# LT6813.net
KiCad netlist of a schematic drawn in Altium Designer
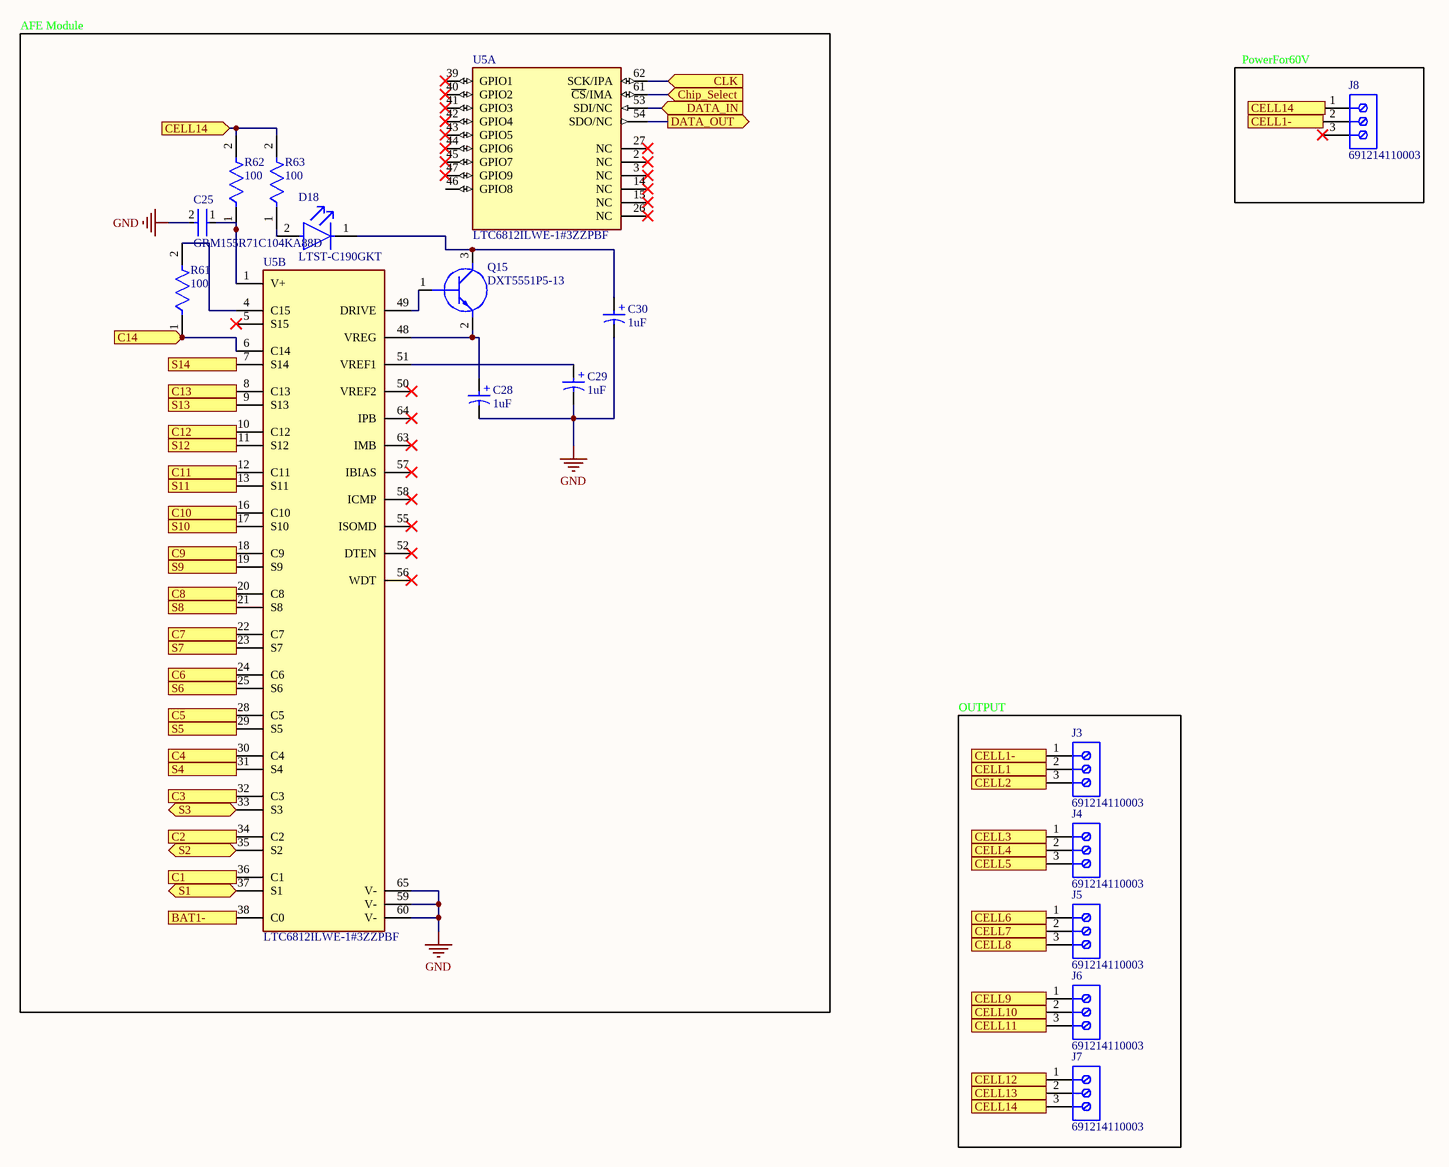
[diagram p0: LT6813.SchDoc]

(export (version "E")
  (design (tool "Eeschema 10.0.6"))
  (components
    (comp (ref "C25")
      (value "GRM155R71C104KA88D")
      (footprint "FP-GRM15-MFG")
      (description "CAP CER 0.1UF 16V X7R 0402")
      (fields
        (field (name "TOLERANCE") "10%")
        (field (name "OCTOPART") "https://octopart.com/grm155r71c104ka88d-murata-196880")
      )
      (libsource (lib "Altium Content Vault") (part "236180d848d6139a670b325ea6854c9"))
    )
    (comp (ref "C28")
      (value "1uF")
      (footprint "WCAP-ASLI_D4H5.5")
      (description "865080840001 Cap, 1Uf, 20%, 100V, Alu Elec Smd Rohs Compliant: Yes")
      (libsource (lib "Altium Content Vault") (part "Capacitor_Polarized"))
    )
    (comp (ref "C29")
      (value "1uF")
      (footprint "WCAP-ASLI_D4H5.5")
      (description "865080840001 Cap, 1Uf, 20%, 100V, Alu Elec Smd Rohs Compliant: Yes")
      (libsource (lib "Altium Content Vault") (part "Capacitor_Polarized"))
    )
    (comp (ref "C30")
      (value "1uF")
      (footprint "WCAP-ASLI_D4H5.5")
      (description "865080840001 Cap, 1Uf, 20%, 100V, Alu Elec Smd Rohs Compliant: Yes")
      (libsource (lib "Altium Content Vault") (part "Capacitor_Polarized"))
    )
    (comp (ref "D18")
      (value "LTST-C190GKT")
      (footprint "FP-LTST-C190GKT-MFG")
      (description "LED GREEN CLEAR CHIP SMD")
      (fields (field (name "VOLTAGE") "2V"))
      (libsource (lib "Altium Content Vault") (part "8706943c75ba83719d021d2fdc84c58"))
    )
    (comp (ref "J3")
      (value "691214110003")
      (footprint "691214110003")
      (fields (field (name "VOLTAGE") "300V"))
      (libsource (lib "Altium Content Vault") (part "TBL - 1R - 03P - Screw"))
    )
    (comp (ref "J4")
      (value "691214110003")
      (footprint "691214110003")
      (fields (field (name "VOLTAGE") "300V"))
      (libsource (lib "Altium Content Vault") (part "TBL - 1R - 03P - Screw"))
    )
    (comp (ref "J5")
      (value "691214110003")
      (footprint "691214110003")
      (fields (field (name "VOLTAGE") "300V"))
      (libsource (lib "Altium Content Vault") (part "TBL - 1R - 03P - Screw"))
    )
    (comp (ref "J6")
      (value "691214110003")
      (footprint "691214110003")
      (fields (field (name "VOLTAGE") "300V"))
      (libsource (lib "Altium Content Vault") (part "TBL - 1R - 03P - Screw"))
    )
    (comp (ref "J7")
      (value "691214110003")
      (footprint "691214110003")
      (fields (field (name "VOLTAGE") "300V"))
      (libsource (lib "Altium Content Vault") (part "TBL - 1R - 03P - Screw"))
    )
    (comp (ref "J8")
      (value "691214110003")
      (footprint "691214110003")
      (fields (field (name "VOLTAGE") "300V"))
      (libsource (lib "Altium Content Vault") (part "TBL - 1R - 03P - Screw"))
    )
    (comp (ref "Q15")
      (value "DXT5551P5-13")
      (footprint "SamacSys:DXT5551P513")
      (description "Transistor BJT NPN")
      (fields (field (name "MOUSER PART NUMBER") "522-DXT5551P5-13"))
      (libsource (lib "*") (part "DXT5551P5-13"))
    )
    (comp (ref "R61")
      (value "100")
      (footprint "FP-RR0816-MFG")
      (description "100Ω ±0.5% 0.0625W 1/16W Chip Resistor 0603 (1608 Metric) Thin Film")
      (fields (field (name "TOLERANCE") "0.5%"))
      (libsource (lib "Altium Content Vault") (part "1029c3af85768c4190bb7ad29bc67b5"))
    )
    (comp (ref "R62")
      (value "100")
      (footprint "FP-RR0816-MFG")
      (description "100Ω ±0.5% 0.0625W 1/16W Chip Resistor 0603 (1608 Metric) Thin Film")
      (fields (field (name "TOLERANCE") "0.5%"))
      (libsource (lib "Altium Content Vault") (part "1029c3af85768c4190bb7ad29bc67b5"))
    )
    (comp (ref "R63")
      (value "100")
      (footprint "FP-RR0816-MFG")
      (description "100Ω ±0.5% 0.0625W 1/16W Chip Resistor 0603 (1608 Metric) Thin Film")
      (fields (field (name "TOLERANCE") "0.5%"))
      (libsource (lib "Altium Content Vault") (part "1029c3af85768c4190bb7ad29bc67b5"))
    )
    (comp (ref "U5")
      (value "LTC6812ILWE-1#3ZZPBF")
      (footprint "FP-LWE-64-05-08-1982-MFG")
      (description "MULTICELL BAT MON S")
      (fields
        (field (name "MANUFACTURER") "Analog Devices")
        (field (name "OCTOPART") "https://octopart.com/ltc6812ilwe-1%233zzpbf-analog+devices-97359568")
      )
      (libsource (lib "Altium Content Vault") (part "304f8939b11d0bec79fdbed9c933bb7"))
    )
  )
  (nets
    (net (code "1") (name "/BAT1-") (class "Default")
      (node (ref "U5") (pin "38") (pinfunction "C0_38") (pintype "passive"))
    )
    (net (code "2") (name "/C1") (class "Default")
      (node (ref "U5") (pin "36") (pinfunction "C1_36") (pintype "passive"))
    )
    (net (code "3") (name "/C2") (class "Default")
      (node (ref "U5") (pin "34") (pinfunction "C2_34") (pintype "passive"))
    )
    (net (code "4") (name "/C3") (class "Default")
      (node (ref "U5") (pin "32") (pinfunction "C3_32") (pintype "passive"))
    )
    (net (code "5") (name "/C4") (class "Default")
      (node (ref "U5") (pin "30") (pinfunction "C4_30") (pintype "passive"))
    )
    (net (code "6") (name "/C5") (class "Default")
      (node (ref "U5") (pin "28") (pinfunction "C5_28") (pintype "passive"))
    )
    (net (code "7") (name "/C6") (class "Default")
      (node (ref "U5") (pin "24") (pinfunction "C6_24") (pintype "passive"))
    )
    (net (code "8") (name "/C7") (class "Default")
      (node (ref "U5") (pin "22") (pinfunction "C7_22") (pintype "passive"))
    )
    (net (code "9") (name "/C8") (class "Default")
      (node (ref "U5") (pin "20") (pinfunction "C8_20") (pintype "passive"))
    )
    (net (code "10") (name "/C9") (class "Default")
      (node (ref "U5") (pin "18") (pinfunction "C9_18") (pintype "passive"))
    )
    (net (code "11") (name "/C10") (class "Default")
      (node (ref "U5") (pin "16") (pinfunction "C10_16") (pintype "passive"))
    )
    (net (code "12") (name "/C11") (class "Default")
      (node (ref "U5") (pin "12") (pinfunction "C11_12") (pintype "passive"))
    )
    (net (code "13") (name "/C12") (class "Default")
      (node (ref "U5") (pin "10") (pinfunction "C12_10") (pintype "passive"))
    )
    (net (code "14") (name "/C13") (class "Default")
      (node (ref "U5") (pin "8") (pinfunction "C13_8") (pintype "passive"))
    )
    (net (code "15") (name "/C14") (class "Default")
      (node (ref "R61") (pin "1") (pinfunction "1_1") (pintype "passive"))
      (node (ref "U5") (pin "6") (pinfunction "C14_6") (pintype "passive"))
    )
    (net (code "16") (name "/CELL1") (class "Default")
      (node (ref "J3") (pin "2") (pinfunction "2_2") (pintype "passive"))
    )
    (net (code "17") (name "/CELL1-") (class "Default")
      (node (ref "J3") (pin "1") (pinfunction "1_1") (pintype "passive"))
      (node (ref "J8") (pin "2") (pinfunction "2_2") (pintype "passive"))
    )
    (net (code "18") (name "/CELL2") (class "Default")
      (node (ref "J3") (pin "3") (pinfunction "3_3") (pintype "passive"))
    )
    (net (code "19") (name "/CELL3") (class "Default")
      (node (ref "J4") (pin "1") (pinfunction "1_1") (pintype "passive"))
    )
    (net (code "20") (name "/CELL4") (class "Default")
      (node (ref "J4") (pin "2") (pinfunction "2_2") (pintype "passive"))
    )
    (net (code "21") (name "/CELL5") (class "Default")
      (node (ref "J4") (pin "3") (pinfunction "3_3") (pintype "passive"))
    )
    (net (code "22") (name "/CELL6") (class "Default")
      (node (ref "J5") (pin "1") (pinfunction "1_1") (pintype "passive"))
    )
    (net (code "23") (name "/CELL7") (class "Default")
      (node (ref "J5") (pin "2") (pinfunction "2_2") (pintype "passive"))
    )
    (net (code "24") (name "/CELL8") (class "Default")
      (node (ref "J5") (pin "3") (pinfunction "3_3") (pintype "passive"))
    )
    (net (code "25") (name "/CELL9") (class "Default")
      (node (ref "J6") (pin "1") (pinfunction "1_1") (pintype "passive"))
    )
    (net (code "26") (name "/CELL10") (class "Default")
      (node (ref "J6") (pin "2") (pinfunction "2_2") (pintype "passive"))
    )
    (net (code "27") (name "/CELL11") (class "Default")
      (node (ref "J6") (pin "3") (pinfunction "3_3") (pintype "passive"))
    )
    (net (code "28") (name "/CELL12") (class "Default")
      (node (ref "J7") (pin "1") (pinfunction "1_1") (pintype "passive"))
    )
    (net (code "29") (name "/CELL13") (class "Default")
      (node (ref "J7") (pin "2") (pinfunction "2_2") (pintype "passive"))
    )
    (net (code "30") (name "/CELL14") (class "Default")
      (node (ref "J7") (pin "3") (pinfunction "3_3") (pintype "passive"))
      (node (ref "R62") (pin "2") (pinfunction "2_2") (pintype "passive"))
      (node (ref "R63") (pin "2") (pinfunction "2_2") (pintype "passive"))
    )
    (net (code "31") (name "/CLK") (class "Default")
      (node (ref "U5") (pin "62") (pinfunction "SCK/IPA_62") (pintype "bidirectional"))
    )
    (net (code "32") (name "/Chip_Select") (class "Default")
      (node (ref "U5") (pin "61") (pinfunction "~{CS}/IMA_61") (pintype "bidirectional"))
    )
    (net (code "33") (name "/DATA_IN") (class "Default")
      (node (ref "U5") (pin "53") (pinfunction "SDI/NC_53") (pintype "input"))
    )
    (net (code "34") (name "/DATA_OUT") (class "Default")
      (node (ref "U5") (pin "54") (pinfunction "SDO/NC_54") (pintype "output"))
    )
    (net (code "35") (name "/S1") (class "Default")
      (node (ref "U5") (pin "37") (pinfunction "S1_37") (pintype "passive"))
    )
    (net (code "36") (name "/S2") (class "Default")
      (node (ref "U5") (pin "35") (pinfunction "S2_35") (pintype "passive"))
    )
    (net (code "37") (name "/S3") (class "Default")
      (node (ref "U5") (pin "33") (pinfunction "S3_33") (pintype "passive"))
    )
    (net (code "38") (name "/S4") (class "Default")
      (node (ref "U5") (pin "31") (pinfunction "S4_31") (pintype "passive"))
    )
    (net (code "39") (name "/S5") (class "Default")
      (node (ref "U5") (pin "29") (pinfunction "S5_29") (pintype "passive"))
    )
    (net (code "40") (name "/S6") (class "Default")
      (node (ref "U5") (pin "25") (pinfunction "S6_25") (pintype "passive"))
    )
    (net (code "41") (name "/S7") (class "Default")
      (node (ref "U5") (pin "23") (pinfunction "S7_23") (pintype "passive"))
    )
    (net (code "42") (name "/S8") (class "Default")
      (node (ref "U5") (pin "21") (pinfunction "S8_21") (pintype "passive"))
    )
    (net (code "43") (name "/S9") (class "Default")
      (node (ref "U5") (pin "19") (pinfunction "S9_19") (pintype "passive"))
    )
    (net (code "44") (name "/S10") (class "Default")
      (node (ref "U5") (pin "17") (pinfunction "S10_17") (pintype "passive"))
    )
    (net (code "45") (name "/S11") (class "Default")
      (node (ref "U5") (pin "13") (pinfunction "S11_13") (pintype "passive"))
    )
    (net (code "46") (name "/S12") (class "Default")
      (node (ref "U5") (pin "11") (pinfunction "S12_11") (pintype "passive"))
    )
    (net (code "47") (name "/S13") (class "Default")
      (node (ref "U5") (pin "9") (pinfunction "S13_9") (pintype "passive"))
    )
    (net (code "48") (name "/S14") (class "Default")
      (node (ref "U5") (pin "7") (pinfunction "S14_7") (pintype "passive"))
    )
    (net (code "49") (name "GND") (class "Default")
      (node (ref "C25") (pin "2") (pinfunction "2_2") (pintype "passive"))
      (node (ref "C28") (pin "2") (pinfunction "N_2") (pintype "passive"))
      (node (ref "C29") (pin "2") (pinfunction "N_2") (pintype "passive"))
      (node (ref "C30") (pin "2") (pinfunction "N_2") (pintype "passive"))
      (node (ref "U5") (pin "59") (pinfunction "V-_59") (pintype "power_in"))
      (node (ref "U5") (pin "60") (pinfunction "V-_60") (pintype "power_in"))
      (node (ref "U5") (pin "65") (pinfunction "V-_65") (pintype "power_in"))
    )
    (net (code "50") (name "Net-(C28-P)") (class "Default")
      (node (ref "C28") (pin "1") (pinfunction "P_1") (pintype "passive"))
      (node (ref "Q15") (pin "2") (pinfunction "E_2") (pintype "passive"))
      (node (ref "U5") (pin "48") (pinfunction "VREG_48") (pintype "passive"))
    )
    (net (code "51") (name "Net-(C29-P)") (class "Default")
      (node (ref "C29") (pin "1") (pinfunction "P_1") (pintype "passive"))
      (node (ref "U5") (pin "51") (pinfunction "VREF1_51") (pintype "passive"))
    )
    (net (code "52") (name "Net-(C30-P)") (class "Default")
      (node (ref "C30") (pin "1") (pinfunction "P_1") (pintype "passive"))
      (node (ref "D18") (pin "1") (pinfunction "C_1") (pintype "passive"))
      (node (ref "Q15") (pin "3") (pinfunction "C_3") (pintype "passive"))
    )
    (net (code "53") (name "Net-(D18-A)") (class "Default")
      (node (ref "D18") (pin "2") (pinfunction "A_2") (pintype "passive"))
      (node (ref "R63") (pin "1") (pinfunction "1_1") (pintype "passive"))
    )
    (net (code "54") (name "Net-(Q15-B)") (class "Default")
      (node (ref "Q15") (pin "1") (pinfunction "B_1") (pintype "passive"))
      (node (ref "U5") (pin "49") (pinfunction "DRIVE_49") (pintype "passive"))
    )
    (net (code "55") (name "Net-(U5B-C15)") (class "Default")
      (node (ref "R61") (pin "2") (pinfunction "2_2") (pintype "passive"))
      (node (ref "U5") (pin "4") (pinfunction "C15_4") (pintype "passive"))
    )
    (net (code "56") (name "Net-(U5B-V+)") (class "Default")
      (node (ref "C25") (pin "1") (pinfunction "1_1") (pintype "passive"))
      (node (ref "R62") (pin "1") (pinfunction "1_1") (pintype "passive"))
      (node (ref "U5") (pin "1") (pinfunction "V+_1") (pintype "power_in"))
    )
    (net (code "57") (name "unconnected-(J8-Pad1)") (class "Default")
      (node (ref "J8") (pin "1") (pinfunction "1_1") (pintype "passive"))
    )
    (net (code "58") (name "unconnected-(J8-Pad3)") (class "Default")
      (node (ref "J8") (pin "3") (pinfunction "3_3") (pintype "passive+no_connect"))
    )
    (net (code "59") (name "unconnected-(U5A-GPIO1-Pad39)") (class "Default")
      (node (ref "U5") (pin "39") (pinfunction "GPIO1_39") (pintype "bidirectional+no_connect"))
    )
    (net (code "60") (name "unconnected-(U5A-GPIO2-Pad40)") (class "Default")
      (node (ref "U5") (pin "40") (pinfunction "GPIO2_40") (pintype "bidirectional+no_connect"))
    )
    (net (code "61") (name "unconnected-(U5A-GPIO3-Pad41)") (class "Default")
      (node (ref "U5") (pin "41") (pinfunction "GPIO3_41") (pintype "bidirectional+no_connect"))
    )
    (net (code "62") (name "unconnected-(U5A-GPIO4-Pad42)") (class "Default")
      (node (ref "U5") (pin "42") (pinfunction "GPIO4_42") (pintype "bidirectional+no_connect"))
    )
    (net (code "63") (name "unconnected-(U5A-GPIO5-Pad43)") (class "Default")
      (node (ref "U5") (pin "43") (pinfunction "GPIO5_43") (pintype "bidirectional+no_connect"))
    )
    (net (code "64") (name "unconnected-(U5A-GPIO6-Pad44)") (class "Default")
      (node (ref "U5") (pin "44") (pinfunction "GPIO6_44") (pintype "bidirectional+no_connect"))
    )
    (net (code "65") (name "unconnected-(U5A-GPIO7-Pad45)") (class "Default")
      (node (ref "U5") (pin "45") (pinfunction "GPIO7_45") (pintype "bidirectional+no_connect"))
    )
    (net (code "66") (name "unconnected-(U5A-GPIO8-Pad46)") (class "Default")
      (node (ref "U5") (pin "46") (pinfunction "GPIO8_46") (pintype "bidirectional"))
    )
    (net (code "67") (name "unconnected-(U5A-GPIO9-Pad47)") (class "Default")
      (node (ref "U5") (pin "47") (pinfunction "GPIO9_47") (pintype "bidirectional+no_connect"))
    )
    (net (code "68") (name "unconnected-(U5A-NC-Pad2)") (class "Default")
      (node (ref "U5") (pin "2") (pinfunction "NC_2") (pintype "passive+no_connect"))
    )
    (net (code "69") (name "unconnected-(U5A-NC-Pad3)") (class "Default")
      (node (ref "U5") (pin "3") (pinfunction "NC_3") (pintype "passive+no_connect"))
    )
    (net (code "70") (name "unconnected-(U5A-NC-Pad14)") (class "Default")
      (node (ref "U5") (pin "14") (pinfunction "NC_14") (pintype "passive+no_connect"))
    )
    (net (code "71") (name "unconnected-(U5A-NC-Pad15)") (class "Default")
      (node (ref "U5") (pin "15") (pinfunction "NC_15") (pintype "passive+no_connect"))
    )
    (net (code "72") (name "unconnected-(U5A-NC-Pad26)") (class "Default")
      (node (ref "U5") (pin "26") (pinfunction "NC_26") (pintype "passive+no_connect"))
    )
    (net (code "73") (name "unconnected-(U5A-NC-Pad27)") (class "Default")
      (node (ref "U5") (pin "27") (pinfunction "NC_27") (pintype "passive+no_connect"))
    )
    (net (code "74") (name "unconnected-(U5B-DTEN-Pad52)") (class "Default")
      (node (ref "U5") (pin "52") (pinfunction "DTEN_52") (pintype "passive+no_connect"))
    )
    (net (code "75") (name "unconnected-(U5B-IBIAS-Pad57)") (class "Default")
      (node (ref "U5") (pin "57") (pinfunction "IBIAS_57") (pintype "passive+no_connect"))
    )
    (net (code "76") (name "unconnected-(U5B-ICMP-Pad58)") (class "Default")
      (node (ref "U5") (pin "58") (pinfunction "ICMP_58") (pintype "passive+no_connect"))
    )
    (net (code "77") (name "unconnected-(U5B-IMB-Pad63)") (class "Default")
      (node (ref "U5") (pin "63") (pinfunction "IMB_63") (pintype "passive+no_connect"))
    )
    (net (code "78") (name "unconnected-(U5B-IPB-Pad64)") (class "Default")
      (node (ref "U5") (pin "64") (pinfunction "IPB_64") (pintype "passive+no_connect"))
    )
    (net (code "79") (name "unconnected-(U5B-ISOMD-Pad55)") (class "Default")
      (node (ref "U5") (pin "55") (pinfunction "ISOMD_55") (pintype "passive+no_connect"))
    )
    (net (code "80") (name "unconnected-(U5B-S15-Pad5)") (class "Default")
      (node (ref "U5") (pin "5") (pinfunction "S15_5") (pintype "passive+no_connect"))
    )
    (net (code "81") (name "unconnected-(U5B-VREF2-Pad50)") (class "Default")
      (node (ref "U5") (pin "50") (pinfunction "VREF2_50") (pintype "passive+no_connect"))
    )
    (net (code "82") (name "unconnected-(U5B-WDT-Pad56)") (class "Default")
      (node (ref "U5") (pin "56") (pinfunction "WDT_56") (pintype "open_collector+no_connect"))
    )
  )
)
